# Z-Axis_Stepper_Motor_Driver.net
KiCad netlist of a schematic drawn in Altium Designer
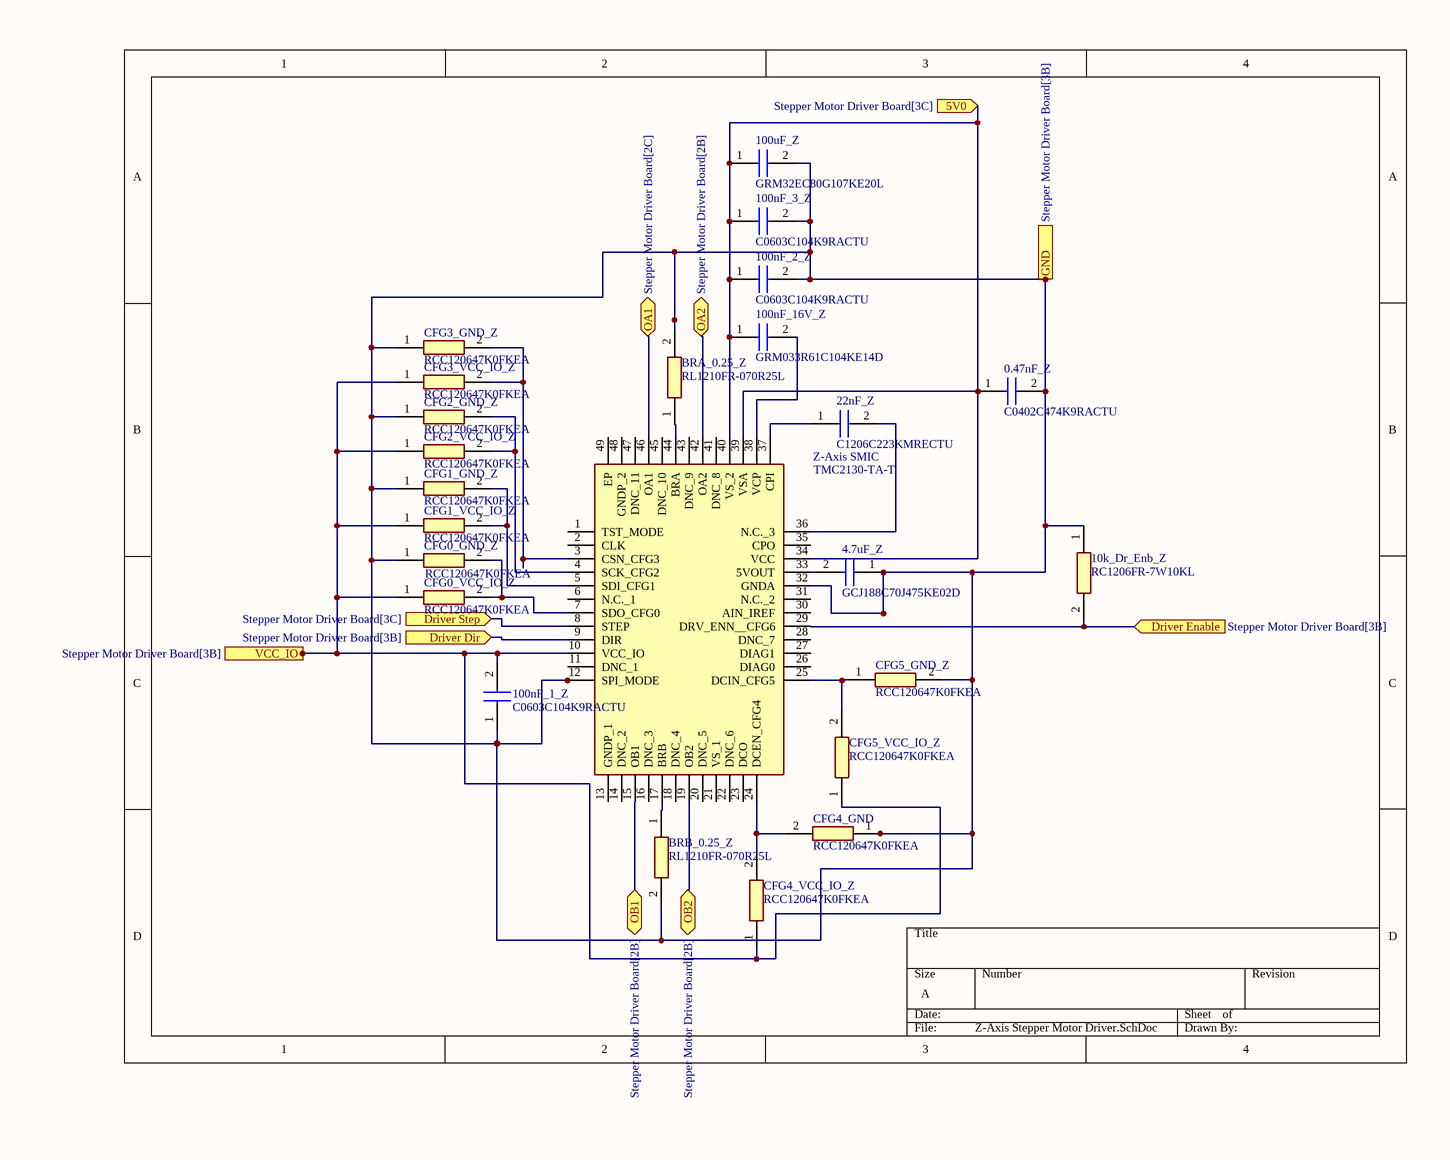
[diagram p0: Z-Axis Stepper Motor Driver.SchDoc]

(export (version "E")
  (design (tool "Eeschema 10.0.6"))
  (components
    (comp (ref "0.47nF_Z")
      (value "C0402C474K9RACTU")
      (footprint "SamacSys:CAPC1005X55N")
      (description "Capacitor")
      (fields (field (name "MOUSER PART NUMBER") "80-C0402C474K9RACTU"))
      (libsource (lib "*") (part "C0402C474K9RACTU"))
    )
    (comp (ref "4.7uF_Z")
      (value "GCJ188C70J475KE02D")
      (footprint "SamacSys:CAPC1608X100N")
      (description "Capacitor")
      (fields (field (name "MOUSER PART NUMBER") "81-GCJ188C70J475KE2D"))
      (libsource (lib "*") (part "GCJ188C70J475KE02D"))
    )
    (comp (ref "10k_Dr_Enb_Z")
      (value "RC1206FR-7W10KL")
      (footprint "SamacSys:RESC3116X65N")
      (description "Resistor")
      (libsource (lib "*") (part "RC1206FR-7W10KL"))
    )
    (comp (ref "22nF_Z")
      (value "C1206C223KMRECTU")
      (footprint "SamacSys:C1206")
      (description "Capacitor")
      (fields (field (name "MOUSER PART NUMBER") "80-C1206C223KMRECTU"))
      (libsource (lib "*") (part "C1206C223KMRECTU"))
    )
    (comp (ref "100nF_1_Z")
      (value "C0603C104K9RACTU")
      (footprint "SamacSys:C0603")
      (description "Capacitor")
      (fields (field (name "MOUSER PART NUMBER") "80-C0603C104K9R"))
      (libsource (lib "*") (part "C0603C104K9RACTU"))
    )
    (comp (ref "100nF_2_Z")
      (value "C0603C104K9RACTU")
      (footprint "SamacSys:C0603")
      (description "Capacitor")
      (fields (field (name "MOUSER PART NUMBER") "80-C0603C104K9R"))
      (libsource (lib "*") (part "C0603C104K9RACTU"))
    )
    (comp (ref "100nF_3_Z")
      (value "C0603C104K9RACTU")
      (footprint "SamacSys:C0603")
      (description "Capacitor")
      (fields (field (name "MOUSER PART NUMBER") "80-C0603C104K9R"))
      (libsource (lib "*") (part "C0603C104K9RACTU"))
    )
    (comp (ref "100nF_16V_Z")
      (value "GRM033R61C104KE14D")
      (footprint "SamacSys:CAPC0603X33N")
      (description "Capacitor")
      (fields (field (name "MOUSER PART NUMBER") "81-GRM033R61C104KE4D"))
      (libsource (lib "*") (part "GRM033R61C104KE14D"))
    )
    (comp (ref "100uF_Z")
      (value "GRM32EC80G107KE20L")
      (footprint "SamacSys:CAPC3225X270N")
      (description "Capacitor")
      (fields (field (name "MOUSER PART NUMBER") "81-GRM32EC80G107KE0L"))
      (libsource (lib "*") (part "GRM32EC80G107KE20L"))
    )
    (comp (ref "BRA_0.25_Z")
      (value "RL1210FR-070R25L")
      (footprint "SamacSys:RESC3126X65N")
      (description "Resistor")
      (fields (field (name "MOUSER PART NUMBER") "603-RL1210FR-070R25L"))
      (libsource (lib "*") (part "RL1210FR-070R25L"))
    )
    (comp (ref "BRB_0.25_Z")
      (value "RL1210FR-070R25L")
      (footprint "SamacSys:RESC3126X65N")
      (description "Resistor")
      (fields (field (name "MOUSER PART NUMBER") "603-RL1210FR-070R25L"))
      (libsource (lib "") (part "RL1210FR-070R25L_1"))
    )
    (comp (ref "CFG0_GND_Z")
      (value "RCC120647K0FKEA")
      (footprint "SamacSys:RCC1206_e3")
      (description "Resistor")
      (fields (field (name "MOUSER PART NUMBER") "71-RCC120647K0FKEA"))
      (libsource (lib "*") (part "RCC120647K0FKEA"))
    )
    (comp (ref "CFG0_VCC_IO_Z")
      (value "RCC120647K0FKEA")
      (footprint "SamacSys:RCC1206_e3")
      (description "Resistor")
      (fields (field (name "MOUSER PART NUMBER") "71-RCC120647K0FKEA"))
      (libsource (lib "*") (part "RCC120647K0FKEA"))
    )
    (comp (ref "CFG1_GND_Z")
      (value "RCC120647K0FKEA")
      (footprint "SamacSys:RCC1206_e3")
      (description "Resistor")
      (fields (field (name "MOUSER PART NUMBER") "71-RCC120647K0FKEA"))
      (libsource (lib "*") (part "RCC120647K0FKEA"))
    )
    (comp (ref "CFG1_VCC_IO_Z")
      (value "RCC120647K0FKEA")
      (footprint "SamacSys:RCC1206_e3")
      (description "Resistor")
      (fields (field (name "MOUSER PART NUMBER") "71-RCC120647K0FKEA"))
      (libsource (lib "*") (part "RCC120647K0FKEA"))
    )
    (comp (ref "CFG2_GND_Z")
      (value "RCC120647K0FKEA")
      (footprint "SamacSys:RCC1206_e3")
      (description "Resistor")
      (fields (field (name "MOUSER PART NUMBER") "71-RCC120647K0FKEA"))
      (libsource (lib "*") (part "RCC120647K0FKEA"))
    )
    (comp (ref "CFG2_VCC_IO_Z")
      (value "RCC120647K0FKEA")
      (footprint "SamacSys:RCC1206_e3")
      (description "Resistor")
      (fields (field (name "MOUSER PART NUMBER") "71-RCC120647K0FKEA"))
      (libsource (lib "*") (part "RCC120647K0FKEA"))
    )
    (comp (ref "CFG3_GND_Z")
      (value "RCC120647K0FKEA")
      (footprint "SamacSys:RCC1206_e3")
      (description "Resistor")
      (fields (field (name "MOUSER PART NUMBER") "71-RCC120647K0FKEA"))
      (libsource (lib "*") (part "RCC120647K0FKEA"))
    )
    (comp (ref "CFG3_VCC_IO_Z")
      (value "RCC120647K0FKEA")
      (footprint "SamacSys:RCC1206_e3")
      (description "Resistor")
      (fields (field (name "MOUSER PART NUMBER") "71-RCC120647K0FKEA"))
      (libsource (lib "*") (part "RCC120647K0FKEA"))
    )
    (comp (ref "CFG4_GND")
      (value "RCC120647K0FKEA")
      (footprint "SamacSys:RCC1206_e3")
      (description "Resistor")
      (fields (field (name "MOUSER PART NUMBER") "71-RCC120647K0FKEA"))
      (libsource (lib "") (part "RCC120647K0FKEA_1"))
    )
    (comp (ref "CFG4_VCC_IO_Z")
      (value "RCC120647K0FKEA")
      (footprint "SamacSys:RCC1206_e3")
      (description "Resistor")
      (fields (field (name "MOUSER PART NUMBER") "71-RCC120647K0FKEA"))
      (libsource (lib "") (part "RCC120647K0FKEA_2"))
    )
    (comp (ref "CFG5_GND_Z")
      (value "RCC120647K0FKEA")
      (footprint "SamacSys:RCC1206_e3")
      (description "Resistor")
      (fields (field (name "MOUSER PART NUMBER") "71-RCC120647K0FKEA"))
      (libsource (lib "*") (part "RCC120647K0FKEA"))
    )
    (comp (ref "CFG5_VCC_IO_Z")
      (value "RCC120647K0FKEA")
      (footprint "SamacSys:RCC1206_e3")
      (description "Resistor")
      (fields (field (name "MOUSER PART NUMBER") "71-RCC120647K0FKEA"))
      (libsource (lib "") (part "RCC120647K0FKEA_2"))
    )
    (comp (ref "Z-Axis SMIC")
      (value "TMC2130-TA-T")
      (footprint "SamacSys:QFP50P900X900X120-49N")
      (description "Integrated Circuit")
      (fields (field (name "MOUSER PART NUMBER") "700-TMC2130-TA-T"))
      (libsource (lib "*") (part "TMC2130-TA-T"))
    )
  )
  (nets
    (net (code "1") (name "/5V0") (class "Default")
      (node (ref "0.47nF_Z") (pin "1") (pinfunction "1_1") (pintype "passive"))
      (node (ref "100nF_16V_Z") (pin "1") (pinfunction "1_1") (pintype "passive"))
      (node (ref "100nF_2_Z") (pin "1") (pinfunction "1_1") (pintype "passive"))
      (node (ref "100nF_3_Z") (pin "1") (pinfunction "1_1") (pintype "passive"))
      (node (ref "100uF_Z") (pin "1") (pinfunction "1_1") (pintype "passive"))
      (node (ref "Z-Axis SMIC") (pin "34") (pinfunction "VCC_34") (pintype "passive"))
      (node (ref "Z-Axis SMIC") (pin "39") (pinfunction "VSA_39") (pintype "passive"))
      (node (ref "Z-Axis SMIC") (pin "40") (pinfunction "VS_2_40") (pintype "passive"))
    )
    (net (code "2") (name "/Driver Dir") (class "Default")
      (node (ref "Z-Axis SMIC") (pin "9") (pinfunction "DIR_9") (pintype "passive"))
    )
    (net (code "3") (name "/Driver Enable") (class "Default")
      (node (ref "10k_Dr_Enb_Z") (pin "2") (pinfunction "2_2") (pintype "passive"))
      (node (ref "Z-Axis SMIC") (pin "29") (pinfunction "DRV_ENN__CFG6_29") (pintype "passive"))
    )
    (net (code "4") (name "/Driver Step") (class "Default")
      (node (ref "Z-Axis SMIC") (pin "8") (pinfunction "STEP_8") (pintype "passive"))
    )
    (net (code "5") (name "/GND") (class "Default")
      (node (ref "0.47nF_Z") (pin "2") (pinfunction "2_2") (pintype "passive"))
      (node (ref "100nF_1_Z") (pin "1") (pinfunction "1_1") (pintype "passive"))
      (node (ref "100nF_2_Z") (pin "2") (pinfunction "2_2") (pintype "passive"))
      (node (ref "100nF_3_Z") (pin "2") (pinfunction "2_2") (pintype "passive"))
      (node (ref "100uF_Z") (pin "2") (pinfunction "2_2") (pintype "passive"))
      (node (ref "10k_Dr_Enb_Z") (pin "1") (pinfunction "1_1") (pintype "passive"))
      (node (ref "4.7uF_Z") (pin "1") (pinfunction "1_1") (pintype "passive"))
      (node (ref "BRA_0.25_Z") (pin "2") (pinfunction "2_2") (pintype "passive"))
      (node (ref "BRB_0.25_Z") (pin "2") (pinfunction "2_2") (pintype "passive"))
      (node (ref "CFG0_GND_Z") (pin "1") (pinfunction "1_1") (pintype "passive"))
      (node (ref "CFG1_GND_Z") (pin "1") (pinfunction "1_1") (pintype "passive"))
      (node (ref "CFG2_GND_Z") (pin "1") (pinfunction "1_1") (pintype "passive"))
      (node (ref "CFG3_GND_Z") (pin "1") (pinfunction "1_1") (pintype "passive"))
      (node (ref "CFG4_GND") (pin "1") (pinfunction "1_1") (pintype "passive"))
      (node (ref "CFG5_GND_Z") (pin "2") (pinfunction "2_2") (pintype "passive"))
      (node (ref "Z-Axis SMIC") (pin "12") (pinfunction "SPI_MODE_12") (pintype "passive"))
      (node (ref "Z-Axis SMIC") (pin "32") (pinfunction "GNDA_32") (pintype "passive"))
    )
    (net (code "6") (name "/OA1") (class "Default")
      (node (ref "Z-Axis SMIC") (pin "46") (pinfunction "OA1_46") (pintype "passive"))
    )
    (net (code "7") (name "/OA2") (class "Default")
      (node (ref "Z-Axis SMIC") (pin "42") (pinfunction "OA2_42") (pintype "passive"))
    )
    (net (code "8") (name "/OB1") (class "Default")
      (node (ref "Z-Axis SMIC") (pin "15") (pinfunction "OB1_15") (pintype "passive"))
    )
    (net (code "9") (name "/OB2") (class "Default")
      (node (ref "Z-Axis SMIC") (pin "19") (pinfunction "OB2_19") (pintype "passive"))
    )
    (net (code "10") (name "/VCC_IO") (class "Default")
      (node (ref "100nF_1_Z") (pin "2") (pinfunction "2_2") (pintype "passive"))
      (node (ref "CFG0_VCC_IO_Z") (pin "1") (pinfunction "1_1") (pintype "passive"))
      (node (ref "CFG1_VCC_IO_Z") (pin "1") (pinfunction "1_1") (pintype "passive"))
      (node (ref "CFG2_VCC_IO_Z") (pin "1") (pinfunction "1_1") (pintype "passive"))
      (node (ref "CFG3_VCC_IO_Z") (pin "1") (pinfunction "1_1") (pintype "passive"))
      (node (ref "CFG4_VCC_IO_Z") (pin "1") (pinfunction "1_1") (pintype "passive"))
      (node (ref "CFG5_VCC_IO_Z") (pin "1") (pinfunction "1_1") (pintype "passive"))
      (node (ref "Z-Axis SMIC") (pin "10") (pinfunction "VCC_IO_10") (pintype "passive"))
    )
    (net (code "11") (name "Net-(Z-Axis SMIC-5VOUT)") (class "Default")
      (node (ref "4.7uF_Z") (pin "2") (pinfunction "2_2") (pintype "passive"))
      (node (ref "Z-Axis SMIC") (pin "33") (pinfunction "5VOUT_33") (pintype "passive"))
    )
    (net (code "12") (name "Net-(Z-Axis SMIC-BRA)") (class "Default")
      (node (ref "BRA_0.25_Z") (pin "1") (pinfunction "1_1") (pintype "passive"))
      (node (ref "Z-Axis SMIC") (pin "44") (pinfunction "BRA_44") (pintype "passive"))
    )
    (net (code "13") (name "Net-(Z-Axis SMIC-BRB)") (class "Default")
      (node (ref "BRB_0.25_Z") (pin "1") (pinfunction "1_1") (pintype "passive"))
      (node (ref "Z-Axis SMIC") (pin "17") (pinfunction "BRB_17") (pintype "passive"))
    )
    (net (code "14") (name "Net-(Z-Axis SMIC-CPI)") (class "Default")
      (node (ref "22nF_Z") (pin "1") (pinfunction "1_1") (pintype "passive"))
      (node (ref "Z-Axis SMIC") (pin "37") (pinfunction "CPI_37") (pintype "passive"))
    )
    (net (code "15") (name "Net-(Z-Axis SMIC-CSN_CFG3)") (class "Default")
      (node (ref "CFG3_GND_Z") (pin "2") (pinfunction "2_2") (pintype "passive"))
      (node (ref "CFG3_VCC_IO_Z") (pin "2") (pinfunction "2_2") (pintype "passive"))
      (node (ref "Z-Axis SMIC") (pin "3") (pinfunction "CSN_CFG3_3") (pintype "passive"))
    )
    (net (code "16") (name "Net-(Z-Axis SMIC-DCEN_CFG4)") (class "Default")
      (node (ref "CFG4_GND") (pin "2") (pinfunction "2_2") (pintype "passive"))
      (node (ref "CFG4_VCC_IO_Z") (pin "2") (pinfunction "2_2") (pintype "passive"))
      (node (ref "Z-Axis SMIC") (pin "24") (pinfunction "DCEN_CFG4_24") (pintype "passive"))
    )
    (net (code "17") (name "Net-(Z-Axis SMIC-DCIN_CFG5)") (class "Default")
      (node (ref "CFG5_GND_Z") (pin "1") (pinfunction "1_1") (pintype "passive"))
      (node (ref "CFG5_VCC_IO_Z") (pin "2") (pinfunction "2_2") (pintype "passive"))
      (node (ref "Z-Axis SMIC") (pin "25") (pinfunction "DCIN_CFG5_25") (pintype "passive"))
    )
    (net (code "18") (name "Net-(Z-Axis SMIC-N.C._3)") (class "Default")
      (node (ref "22nF_Z") (pin "2") (pinfunction "2_2") (pintype "passive"))
      (node (ref "Z-Axis SMIC") (pin "36") (pinfunction "N.C._3_36") (pintype "passive"))
    )
    (net (code "19") (name "Net-(Z-Axis SMIC-SCK_CFG2)") (class "Default")
      (node (ref "CFG2_GND_Z") (pin "2") (pinfunction "2_2") (pintype "passive"))
      (node (ref "CFG2_VCC_IO_Z") (pin "2") (pinfunction "2_2") (pintype "passive"))
      (node (ref "Z-Axis SMIC") (pin "4") (pinfunction "SCK_CFG2_4") (pintype "passive"))
    )
    (net (code "20") (name "Net-(Z-Axis SMIC-SDI_CFG1)") (class "Default")
      (node (ref "CFG1_GND_Z") (pin "2") (pinfunction "2_2") (pintype "passive"))
      (node (ref "CFG1_VCC_IO_Z") (pin "2") (pinfunction "2_2") (pintype "passive"))
      (node (ref "Z-Axis SMIC") (pin "5") (pinfunction "SDI_CFG1_5") (pintype "passive"))
    )
    (net (code "21") (name "Net-(Z-Axis SMIC-SDO_CFG0)") (class "Default")
      (node (ref "CFG0_GND_Z") (pin "2") (pinfunction "2_2") (pintype "passive"))
      (node (ref "CFG0_VCC_IO_Z") (pin "2") (pinfunction "2_2") (pintype "passive"))
      (node (ref "Z-Axis SMIC") (pin "7") (pinfunction "SDO_CFG0_7") (pintype "passive"))
    )
    (net (code "22") (name "Net-(Z-Axis SMIC-VCP)") (class "Default")
      (node (ref "100nF_16V_Z") (pin "2") (pinfunction "2_2") (pintype "passive"))
      (node (ref "Z-Axis SMIC") (pin "38") (pinfunction "VCP_38") (pintype "passive"))
    )
    (net (code "23") (name "unconnected-(Z-Axis SMIC-AIN_IREF-Pad30)") (class "Default")
      (node (ref "Z-Axis SMIC") (pin "30") (pinfunction "AIN_IREF_30") (pintype "passive"))
    )
    (net (code "24") (name "unconnected-(Z-Axis SMIC-CLK-Pad2)") (class "Default")
      (node (ref "Z-Axis SMIC") (pin "2") (pinfunction "CLK_2") (pintype "passive"))
    )
    (net (code "25") (name "unconnected-(Z-Axis SMIC-CPO-Pad35)") (class "Default")
      (node (ref "Z-Axis SMIC") (pin "35") (pinfunction "CPO_35") (pintype "passive"))
    )
    (net (code "26") (name "unconnected-(Z-Axis SMIC-DCO-Pad23)") (class "Default")
      (node (ref "Z-Axis SMIC") (pin "23") (pinfunction "DCO_23") (pintype "passive"))
    )
    (net (code "27") (name "unconnected-(Z-Axis SMIC-DIAG0-Pad26)") (class "Default")
      (node (ref "Z-Axis SMIC") (pin "26") (pinfunction "DIAG0_26") (pintype "passive"))
    )
    (net (code "28") (name "unconnected-(Z-Axis SMIC-DIAG1-Pad27)") (class "Default")
      (node (ref "Z-Axis SMIC") (pin "27") (pinfunction "DIAG1_27") (pintype "passive"))
    )
    (net (code "29") (name "unconnected-(Z-Axis SMIC-DNC_1-Pad11)") (class "Default")
      (node (ref "Z-Axis SMIC") (pin "11") (pinfunction "DNC_1_11") (pintype "passive"))
    )
    (net (code "30") (name "unconnected-(Z-Axis SMIC-DNC_2-Pad14)") (class "Default")
      (node (ref "Z-Axis SMIC") (pin "14") (pinfunction "DNC_2_14") (pintype "passive"))
    )
    (net (code "31") (name "unconnected-(Z-Axis SMIC-DNC_3-Pad16)") (class "Default")
      (node (ref "Z-Axis SMIC") (pin "16") (pinfunction "DNC_3_16") (pintype "passive"))
    )
    (net (code "32") (name "unconnected-(Z-Axis SMIC-DNC_4-Pad18)") (class "Default")
      (node (ref "Z-Axis SMIC") (pin "18") (pinfunction "DNC_4_18") (pintype "passive"))
    )
    (net (code "33") (name "unconnected-(Z-Axis SMIC-DNC_5-Pad20)") (class "Default")
      (node (ref "Z-Axis SMIC") (pin "20") (pinfunction "DNC_5_20") (pintype "passive"))
    )
    (net (code "34") (name "unconnected-(Z-Axis SMIC-DNC_6-Pad22)") (class "Default")
      (node (ref "Z-Axis SMIC") (pin "22") (pinfunction "DNC_6_22") (pintype "passive"))
    )
    (net (code "35") (name "unconnected-(Z-Axis SMIC-DNC_7-Pad28)") (class "Default")
      (node (ref "Z-Axis SMIC") (pin "28") (pinfunction "DNC_7_28") (pintype "passive"))
    )
    (net (code "36") (name "unconnected-(Z-Axis SMIC-DNC_8-Pad41)") (class "Default")
      (node (ref "Z-Axis SMIC") (pin "41") (pinfunction "DNC_8_41") (pintype "passive"))
    )
    (net (code "37") (name "unconnected-(Z-Axis SMIC-DNC_9-Pad43)") (class "Default")
      (node (ref "Z-Axis SMIC") (pin "43") (pinfunction "DNC_9_43") (pintype "passive"))
    )
    (net (code "38") (name "unconnected-(Z-Axis SMIC-DNC_10-Pad45)") (class "Default")
      (node (ref "Z-Axis SMIC") (pin "45") (pinfunction "DNC_10_45") (pintype "passive"))
    )
    (net (code "39") (name "unconnected-(Z-Axis SMIC-DNC_11-Pad47)") (class "Default")
      (node (ref "Z-Axis SMIC") (pin "47") (pinfunction "DNC_11_47") (pintype "passive"))
    )
    (net (code "40") (name "unconnected-(Z-Axis SMIC-EP-Pad49)") (class "Default")
      (node (ref "Z-Axis SMIC") (pin "49") (pinfunction "EP_49") (pintype "passive"))
    )
    (net (code "41") (name "unconnected-(Z-Axis SMIC-GNDP_1-Pad13)") (class "Default")
      (node (ref "Z-Axis SMIC") (pin "13") (pinfunction "GNDP_1_13") (pintype "passive"))
    )
    (net (code "42") (name "unconnected-(Z-Axis SMIC-GNDP_2-Pad48)") (class "Default")
      (node (ref "Z-Axis SMIC") (pin "48") (pinfunction "GNDP_2_48") (pintype "passive"))
    )
    (net (code "43") (name "unconnected-(Z-Axis SMIC-N.C._1-Pad6)") (class "Default")
      (node (ref "Z-Axis SMIC") (pin "6") (pinfunction "N.C._1_6") (pintype "passive"))
    )
    (net (code "44") (name "unconnected-(Z-Axis SMIC-N.C._2-Pad31)") (class "Default")
      (node (ref "Z-Axis SMIC") (pin "31") (pinfunction "N.C._2_31") (pintype "passive"))
    )
    (net (code "45") (name "unconnected-(Z-Axis SMIC-TST_MODE-Pad1)") (class "Default")
      (node (ref "Z-Axis SMIC") (pin "1") (pinfunction "TST_MODE_1") (pintype "passive"))
    )
    (net (code "46") (name "unconnected-(Z-Axis SMIC-VS_1-Pad21)") (class "Default")
      (node (ref "Z-Axis SMIC") (pin "21") (pinfunction "VS_1_21") (pintype "passive"))
    )
  )
)
